# 136khz_RX_2025-06-14.net
KiCad netlist of a schematic drawn in EasyEDA Pro
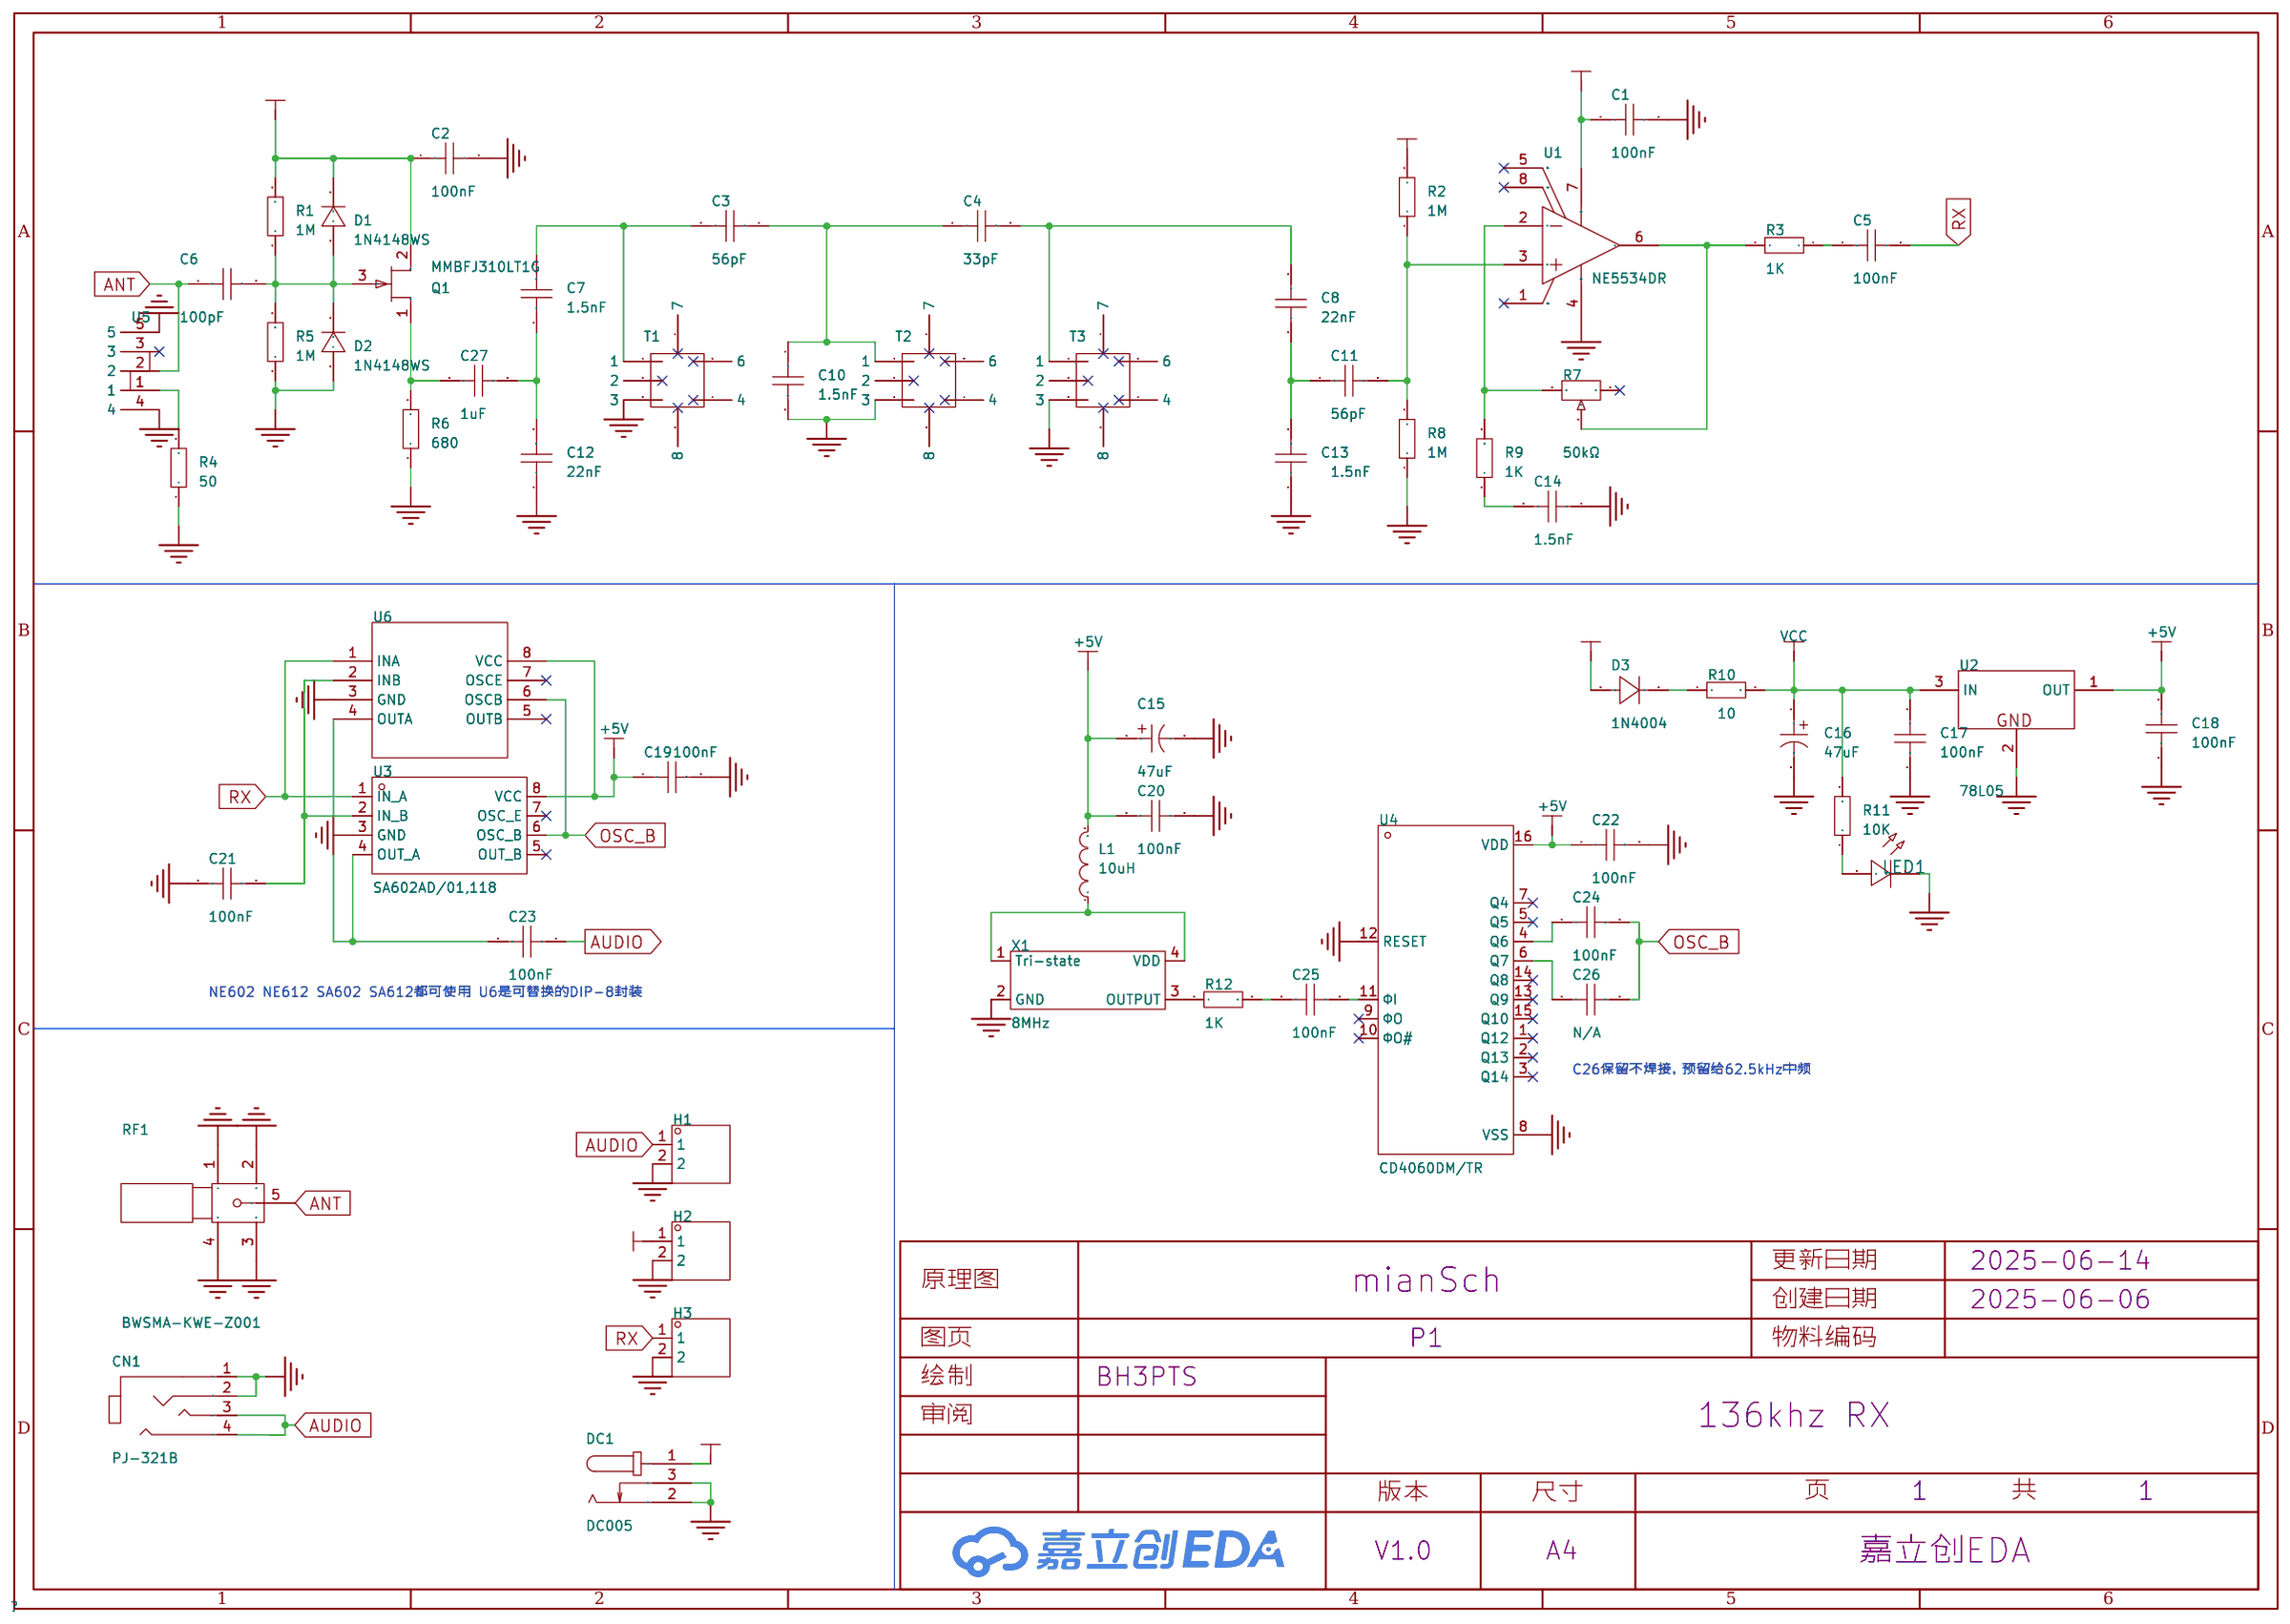
[diagram p0: schematic sheet]

(export (version "E")
  (design (tool "Eeschema 10.0.6"))
  (components
    (comp (ref "C1")
      (value "100nF")
      (footprint "easyedapro:C0805")
      (libsource (lib "easyedapro") (part "CapAcitance"))
    )
    (comp (ref "C2")
      (value "100nF")
      (footprint "easyedapro:C0805")
      (libsource (lib "easyedapro") (part "CapAcitance"))
    )
    (comp (ref "C3")
      (value "56pF")
      (footprint "easyedapro:C0805")
      (libsource (lib "easyedapro") (part "CapAcitance"))
    )
    (comp (ref "C4")
      (value "33pF")
      (footprint "easyedapro:C0805")
      (libsource (lib "easyedapro") (part "CapAcitance"))
    )
    (comp (ref "C5")
      (value "100nF")
      (footprint "easyedapro:C0805")
      (libsource (lib "easyedapro") (part "CapAcitance"))
    )
    (comp (ref "C6")
      (value "100pF")
      (footprint "easyedapro:C0805")
      (libsource (lib "easyedapro") (part "CapAcitance"))
    )
    (comp (ref "C7")
      (value "1.5nF")
      (footprint "easyedapro:C0805")
      (libsource (lib "easyedapro") (part "CapAcitance"))
    )
    (comp (ref "C8")
      (value "22nF")
      (footprint "easyedapro:C0805")
      (libsource (lib "easyedapro") (part "CapAcitance"))
    )
    (comp (ref "C10")
      (value "1.5nF")
      (footprint "easyedapro:C0805")
      (libsource (lib "easyedapro") (part "CapAcitance"))
    )
    (comp (ref "C11")
      (value "56pF")
      (footprint "easyedapro:C0805")
      (libsource (lib "easyedapro") (part "CapAcitance"))
    )
    (comp (ref "C12")
      (value "22nF")
      (footprint "easyedapro:C0805")
      (libsource (lib "easyedapro") (part "CapAcitance"))
    )
    (comp (ref "C13")
      (value "1.5nF")
      (footprint "easyedapro:C0805")
      (libsource (lib "easyedapro") (part "CapAcitance"))
    )
    (comp (ref "C14")
      (value "1.5nF")
      (footprint "easyedapro:C0805")
      (libsource (lib "easyedapro") (part "CapAcitance"))
    )
    (comp (ref "C15")
      (value "47uF")
      (footprint "easyedapro:CAP-SMD_BD6.3-L6.6-W6.6-LS7.2-FD")
      (description "容值:47uF;精度:±20%;额定电压:35V;纹波电流:16.4mA@120Hz;等效串联电阻(ESR):-;")
      (fields
        (field (name "Manufacturer Part") "RVT47UF35V67RV0039")
        (field (name "Manufacturer") "KNSCHA(科尼盛)")
      )
      (libsource (lib "easyedapro") (part "RVT47UF35V67RV0039"))
    )
    (comp (ref "C16")
      (value "47uF")
      (footprint "easyedapro:CAP-SMD_BD6.3-L6.6-W6.6-LS7.2-FD")
      (description "容值:47uF;精度:±20%;额定电压:35V;纹波电流:16.4mA@120Hz;等效串联电阻(ESR):-;")
      (fields
        (field (name "Manufacturer Part") "RVT47UF35V67RV0039")
        (field (name "Manufacturer") "KNSCHA(科尼盛)")
      )
      (libsource (lib "easyedapro") (part "RVT47UF35V67RV0039"))
    )
    (comp (ref "C17")
      (value "100nF")
      (footprint "easyedapro:C0805")
      (libsource (lib "easyedapro") (part "CapAcitance"))
    )
    (comp (ref "C18")
      (value "100nF")
      (footprint "easyedapro:C0805")
      (libsource (lib "easyedapro") (part "CapAcitance"))
    )
    (comp (ref "C19")
      (value "100nF")
      (footprint "easyedapro:C0805")
      (libsource (lib "easyedapro") (part "CapAcitance"))
    )
    (comp (ref "C20")
      (value "100nF")
      (footprint "easyedapro:C0805")
      (libsource (lib "easyedapro") (part "CapAcitance"))
    )
    (comp (ref "C21")
      (value "100nF")
      (footprint "easyedapro:C0805")
      (libsource (lib "easyedapro") (part "CapAcitance"))
    )
    (comp (ref "C22")
      (value "100nF")
      (footprint "easyedapro:C0805")
      (libsource (lib "easyedapro") (part "CapAcitance"))
    )
    (comp (ref "C23")
      (value "100nF")
      (footprint "easyedapro:C0805")
      (libsource (lib "easyedapro") (part "CapAcitance"))
    )
    (comp (ref "C24")
      (value "100nF")
      (footprint "easyedapro:C0805")
      (libsource (lib "easyedapro") (part "CapAcitance"))
    )
    (comp (ref "C25")
      (value "100nF")
      (footprint "easyedapro:C0805")
      (libsource (lib "easyedapro") (part "CapAcitance"))
    )
    (comp (ref "C26")
      (value "N/A")
      (footprint "easyedapro:C0805")
      (libsource (lib "easyedapro") (part "CapAcitance"))
    )
    (comp (ref "C27")
      (value "1uF")
      (footprint "easyedapro:C0805")
      (libsource (lib "easyedapro") (part "CapAcitance"))
    )
    (comp (ref "CN1")
      (value "PJ-321B")
      (footprint "easyedapro:AUDIO-TH_PJ-321B")
      (description "连接器类型:3.5mm耳机座;额定电流:500mA;额定电压:30V;工作温度范围:-20°C~+70°C;焊接温度(最大值):235°C;")
      (fields (field (name "Manufacturer") "XKB Connection(中国星坤)"))
      (libsource (lib "easyedapro") (part "PJ-321B"))
    )
    (comp (ref "D1")
      (value "1N4148WS")
      (footprint "easyedapro:SOD-323_L1.8-W1.3-LS2.5-RD")
      (description "二极管配置:独立式;正向压降(Vf):1.25V@150mA;直流反向耐压(Vr):100V;整流电流:150mA;反向恢复时间(trr):4ns;")
      (fields (field (name "Manufacturer") "CJ(江苏长电/长晶)"))
      (libsource (lib "easyedapro") (part "1N4148WS T4"))
    )
    (comp (ref "D2")
      (value "1N4148WS")
      (footprint "easyedapro:SOD-323_L1.8-W1.3-LS2.5-RD")
      (description "二极管配置:独立式;正向压降(Vf):1.25V@150mA;直流反向耐压(Vr):100V;整流电流:150mA;反向恢复时间(trr):4ns;")
      (fields (field (name "Manufacturer") "CJ(江苏长电/长晶)"))
      (libsource (lib "easyedapro") (part "1N4148WS T4"))
    )
    (comp (ref "D3")
      (value "1N4004")
      (footprint "easyedapro:SMA_L4.4-W2.8-LS5.4-RD")
      (description "二极管配置:独立式;正向压降(Vf):1.1V@1A;直流反向耐压(Vr):400V;整流电流:1A;")
      (fields (field (name "Manufacturer") "TWGMC(台湾迪嘉)"))
      (libsource (lib "easyedapro") (part "1N4004_C727080"))
    )
    (comp (ref "DC1")
      (value "DC005")
      (footprint "easyedapro:DC-IN-TH_DC005")
      (description "连接器类型:DC电源插座;安装方式:弯插;触点内径:2mm;触点外径:6.3mm;额定电流:500mA;额定电压:30V;工作温度范围:-25°C~+70°C;")
      (fields (field (name "Manufacturer") "SHOU HAN(首韩)"))
      (libsource (lib "easyedapro") (part "DC005_C431533"))
    )
    (comp (ref "H1")
      (value "~")
      (footprint "easyedapro:HDR-TH_2P-P2.54-V-M-1")
      (libsource (lib "easyedapro") (part "210S-1*2P L=11.6MMGold-plated black"))
    )
    (comp (ref "H2")
      (value "~")
      (footprint "easyedapro:HDR-TH_2P-P2.54-V-M-1")
      (libsource (lib "easyedapro") (part "210S-1*2P L=11.6MMGold-plated black"))
    )
    (comp (ref "H3")
      (value "~")
      (footprint "easyedapro:HDR-TH_2P-P2.54-V-M-1")
      (libsource (lib "easyedapro") (part "210S-1*2P L=11.6MMGold-plated black"))
    )
    (comp (ref "L1")
      (value "10uH")
      (footprint "easyedapro:L0603")
      (description "电感值:10uH;精度:±10%;额定电流:3mA;饱和电流(Isat):-;直流电阻(DCR):1.85Ω;")
      (fields
        (field (name "Manufacturer Part") "SDFL1608S100KTF")
        (field (name "Manufacturer") "Sunlord(顺络)")
      )
      (libsource (lib "easyedapro") (part "SDFL1608S100KTF"))
    )
    (comp (ref "LED1")
      (value "~")
      (footprint "easyedapro:LED_0603")
      (libsource (lib "easyedapro") (part "LED_R"))
    )
    (comp (ref "Q1")
      (value "MMBFJ310LT1G")
      (footprint "easyedapro:SOT-23-3_L2.9-W1.6-P1.90-LS2.8-BR")
      (description "FET类型:N沟道;栅源击穿电压(V(BR)GSS):-;功率(Pd):-;漏源导通电阻(RDS(on)):-;饱和漏源电流(Idss@Vds,Vgs=0):-;")
      (fields (field (name "Manufacturer") "onsemi(安森美)"))
      (libsource (lib "easyedapro") (part "MMBFJ310LT1G"))
    )
    (comp (ref "R1") (value "1M") (footprint "easyedapro:R0805") (libsource (lib "easyedapro") (part "电阻")))
    (comp (ref "R2") (value "1M") (footprint "easyedapro:R0805") (libsource (lib "easyedapro") (part "电阻")))
    (comp (ref "R3") (value "1K") (footprint "easyedapro:R0805") (libsource (lib "easyedapro") (part "电阻")))
    (comp (ref "R4") (value "50") (footprint "easyedapro:R0805") (libsource (lib "easyedapro") (part "电阻")))
    (comp (ref "R5") (value "1M") (footprint "easyedapro:R0805") (libsource (lib "easyedapro") (part "电阻")))
    (comp (ref "R6") (value "680") (footprint "easyedapro:R0805") (libsource (lib "easyedapro") (part "电阻")))
    (comp (ref "R7")
      (value "50kΩ")
      (footprint "easyedapro:RES-ADJ-TH_3P-L7.1-W6.9-P2.50-L_3362P")
      (description "阻值:50kΩ;精度:±10%;")
      (fields (field (name "Manufacturer Part") "3362P-1-503") (field (name "Manufacturer") "BOCHEN(博晨)"))
      (libsource (lib "easyedapro") (part "3362P-1-503"))
    )
    (comp (ref "R8") (value "1M") (footprint "easyedapro:R0805") (libsource (lib "easyedapro") (part "电阻")))
    (comp (ref "R9") (value "1K") (footprint "easyedapro:R0805") (libsource (lib "easyedapro") (part "电阻")))
    (comp (ref "R10") (value "10") (footprint "easyedapro:R1206") (libsource (lib "easyedapro") (part "电阻")))
    (comp (ref "R11") (value "10K") (footprint "easyedapro:R0805") (libsource (lib "easyedapro") (part "电阻")))
    (comp (ref "R12") (value "1K") (footprint "easyedapro:R0805") (libsource (lib "easyedapro") (part "电阻")))
    (comp (ref "RF1")
      (value "BWSMA-KWE-Z001")
      (footprint "easyedapro:SMA-TH_BWSMA-KWE-Z001")
      (fields (field (name "Manufacturer") "BAT WIRELESS(蝙蝠无线)"))
      (libsource (lib "easyedapro") (part "BWSMA-KWE-Z001"))
    )
    (comp (ref "T1") (value "~") (footprint "easyedapro:TP702") (libsource (lib "easyedapro") (part "TP702")))
    (comp (ref "T2") (value "~") (footprint "easyedapro:TP702") (libsource (lib "easyedapro") (part "TP702")))
    (comp (ref "T3") (value "~") (footprint "easyedapro:TP702") (libsource (lib "easyedapro") (part "TP702")))
    (comp (ref "U1")
      (value "NE5534DR")
      (footprint "easyedapro:SOIC-8_L5.0-W4.0-P1.27-LS6.0-BL")
      (description "放大器数:单路;轨到轨:-;增益带宽积(GBP):-;输入失调电压(Vos):4mV;压摆率(SR):13V/us;输入偏置电流(Ib):1.5uA;")
      (fields (field (name "Manufacturer") "TI(德州仪器)"))
      (libsource (lib "easyedapro") (part "NE5534DR"))
    )
    (comp (ref "U2")
      (value "78L05")
      (footprint "easyedapro:SOT-89-3_L4.5-W2.5-P1.50-LS4.2-BR")
      (description "输出类型:固定;最大输入电压:30V;输出电压:5V;输出电流:100mA;电源纹波抑制比(PSRR):49dB@(120Hz);输出极性:正极;")
      (fields (field (name "Manufacturer") "UMW(友台半导体)"))
      (libsource (lib "easyedapro") (part "UMW78L05"))
    )
    (comp (ref "U3")
      (value "SA602AD/01,118")
      (footprint "easyedapro:SOP-8_L4.9-W3.9-P1.27-LS6.0-BL")
      (description "应用领域:手机；VHF；UHF；HF;频率范围:-;增益:17dB;噪声系数:5dB;")
      (fields (field (name "Manufacturer") "NXP(恩智浦)"))
      (libsource (lib "easyedapro") (part "SA602AD/01,118"))
    )
    (comp (ref "U4")
      (value "CD4060DM/TR")
      (footprint "easyedapro:SOP-16_L9.9-W3.9-P1.27-LS6.0-BL")
      (description "CD4000系列  CMOS 14 级纹波进位二进制计数器/除法器和振荡器")
      (fields (field (name "Manufacturer") "HGSEMI(华冠)"))
      (libsource (lib "easyedapro") (part "CD4060DM/TR"))
    )
    (comp (ref "U5")
      (value "~")
      (footprint "easyedapro:SS-12D07G3")
      (description "3脚2档 柄高3MM")
      (libsource (lib "easyedapro") (part "SS-12D07G3"))
    )
    (comp (ref "U6")
      (value "~")
      (footprint "easyedapro:DIP-8_L9.2-W6.4-P2.54-LS7.6-BL")
      (fields (field (name "Manufacturer") "ddsddp-"))
      (libsource (lib "easyedapro") (part "ne602"))
    )
    (comp (ref "X1")
      (value "8MHz")
      (footprint "easyedapro:OSC-SMD_4P-L3.2-W2.5-BL")
      (description "频率:8MHz;常温频差:±10ppm;输出模式:CMOS;工作电压:5V;频率稳定度:±20ppm;")
      (fields
        (field (name "Manufacturer Part") "OH2EL89CFI-111YLC-8M")
        (field (name "Manufacturer") "YXC(扬兴晶振)")
      )
      (libsource (lib "easyedapro") (part "OH2EL89CFI-111YLC-8M"))
    )
  )
  (nets
    (net (code "1") (name "+5V") (class "Default")
      (node (ref "C15") (pin "1") (pinfunction "1_1") (pintype "input"))
      (node (ref "C18") (pin "2") (pinfunction "2_2") (pintype "input"))
      (node (ref "C19") (pin "1") (pinfunction "1_1") (pintype "input"))
      (node (ref "C20") (pin "2") (pinfunction "2_2") (pintype "input"))
      (node (ref "C22") (pin "1") (pinfunction "1_1") (pintype "input"))
      (node (ref "L1") (pin "2") (pinfunction "2_2") (pintype "unspecified"))
      (node (ref "U2") (pin "1") (pinfunction "OUT_1") (pintype "unspecified"))
      (node (ref "U3") (pin "8") (pinfunction "VCC_8") (pintype "unspecified"))
      (node (ref "U4") (pin "16") (pinfunction "VDD_16") (pintype "unspecified"))
      (node (ref "U6") (pin "8") (pinfunction "VCC_8") (pintype "input"))
    )
    (net (code "2") (name "ANT") (class "Default")
      (node (ref "C6") (pin "1") (pinfunction "1_1") (pintype "input"))
      (node (ref "RF1") (pin "5") (pinfunction "5_5") (pintype "unspecified"))
      (node (ref "U5") (pin "2") (pinfunction "2_2") (pintype "input"))
    )
    (net (code "3") (name "AUDIO") (class "Default")
      (node (ref "C23") (pin "1") (pinfunction "1_1") (pintype "input"))
      (node (ref "CN1") (pin "3") (pinfunction "3_3") (pintype "unspecified"))
      (node (ref "CN1") (pin "4") (pinfunction "4_4") (pintype "unspecified"))
      (node (ref "H1") (pin "1") (pinfunction "1_1") (pintype "unspecified"))
    )
    (net (code "4") (name "GND") (class "Default")
      (node (ref "C1") (pin "2") (pinfunction "2_2") (pintype "input"))
      (node (ref "C10") (pin "2") (pinfunction "2_2") (pintype "input"))
      (node (ref "C12") (pin "1") (pinfunction "1_1") (pintype "input"))
      (node (ref "C13") (pin "1") (pinfunction "1_1") (pintype "input"))
      (node (ref "C14") (pin "1") (pinfunction "1_1") (pintype "input"))
      (node (ref "C15") (pin "2") (pinfunction "2_2") (pintype "input"))
      (node (ref "C16") (pin "2") (pinfunction "2_2") (pintype "input"))
      (node (ref "C17") (pin "1") (pinfunction "1_1") (pintype "input"))
      (node (ref "C18") (pin "1") (pinfunction "1_1") (pintype "input"))
      (node (ref "C19") (pin "2") (pinfunction "2_2") (pintype "input"))
      (node (ref "C2") (pin "2") (pinfunction "2_2") (pintype "input"))
      (node (ref "C20") (pin "1") (pinfunction "1_1") (pintype "input"))
      (node (ref "C21") (pin "1") (pinfunction "1_1") (pintype "input"))
      (node (ref "C22") (pin "2") (pinfunction "2_2") (pintype "input"))
      (node (ref "CN1") (pin "1") (pinfunction "1_1") (pintype "unspecified"))
      (node (ref "CN1") (pin "2") (pinfunction "2_2") (pintype "unspecified"))
      (node (ref "D2") (pin "2") (pinfunction "A_2") (pintype "unspecified"))
      (node (ref "DC1") (pin "2") (pinfunction "2_2") (pintype "unspecified"))
      (node (ref "DC1") (pin "3") (pinfunction "3_3") (pintype "unspecified"))
      (node (ref "H1") (pin "2") (pinfunction "2_2") (pintype "unspecified"))
      (node (ref "H2") (pin "2") (pinfunction "2_2") (pintype "unspecified"))
      (node (ref "H3") (pin "2") (pinfunction "2_2") (pintype "unspecified"))
      (node (ref "LED1") (pin "1") (pinfunction "C_1") (pintype "input"))
      (node (ref "R4") (pin "1") (pinfunction "1_1") (pintype "input"))
      (node (ref "R5") (pin "1") (pinfunction "1_1") (pintype "input"))
      (node (ref "R6") (pin "1") (pinfunction "1_1") (pintype "input"))
      (node (ref "R8") (pin "1") (pinfunction "1_1") (pintype "input"))
      (node (ref "RF1") (pin "1") (pinfunction "1_1") (pintype "unspecified"))
      (node (ref "RF1") (pin "2") (pinfunction "2_2") (pintype "unspecified"))
      (node (ref "RF1") (pin "3") (pinfunction "3_3") (pintype "unspecified"))
      (node (ref "RF1") (pin "4") (pinfunction "4_4") (pintype "unspecified"))
      (node (ref "T1") (pin "3") (pinfunction "3_3") (pintype "input"))
      (node (ref "T2") (pin "3") (pinfunction "3_3") (pintype "input"))
      (node (ref "T3") (pin "3") (pinfunction "3_3") (pintype "input"))
      (node (ref "U1") (pin "4") (pinfunction "VCC-_4") (pintype "unspecified"))
      (node (ref "U2") (pin "2") (pinfunction "GND_2") (pintype "unspecified"))
      (node (ref "U3") (pin "3") (pinfunction "GND_3") (pintype "unspecified"))
      (node (ref "U4") (pin "12") (pinfunction "RESET_12") (pintype "unspecified"))
      (node (ref "U4") (pin "8") (pinfunction "VSS_8") (pintype "unspecified"))
      (node (ref "U5") (pin "4") (pinfunction "4_4") (pintype "input"))
      (node (ref "U5") (pin "5") (pinfunction "5_5") (pintype "input"))
      (node (ref "U6") (pin "3") (pinfunction "GND_3") (pintype "input"))
      (node (ref "X1") (pin "2") (pinfunction "GND_2") (pintype "unspecified"))
    )
    (net (code "5") (name "Net-(C3-Pad2)") (class "Default")
      (node (ref "C3") (pin "2") (pinfunction "2_2") (pintype "input"))
      (node (ref "C7") (pin "2") (pinfunction "2_2") (pintype "input"))
      (node (ref "T1") (pin "1") (pinfunction "1_1") (pintype "input"))
    )
    (net (code "6") (name "Net-(C4-Pad2)") (class "Default")
      (node (ref "C4") (pin "2") (pinfunction "2_2") (pintype "input"))
      (node (ref "C8") (pin "2") (pinfunction "2_2") (pintype "input"))
      (node (ref "T3") (pin "1") (pinfunction "1_1") (pintype "input"))
    )
    (net (code "7") (name "Net-(C5-Pad1)") (class "Default")
      (node (ref "C5") (pin "1") (pinfunction "1_1") (pintype "input"))
      (node (ref "R3") (pin "1") (pinfunction "1_1") (pintype "input"))
    )
    (net (code "8") (name "Net-(C10-Pad1)") (class "Default")
      (node (ref "C10") (pin "1") (pinfunction "1_1") (pintype "input"))
      (node (ref "C3") (pin "1") (pinfunction "1_1") (pintype "input"))
      (node (ref "C4") (pin "1") (pinfunction "1_1") (pintype "input"))
      (node (ref "T2") (pin "1") (pinfunction "1_1") (pintype "input"))
    )
    (net (code "9") (name "Net-(C11-Pad1)") (class "Default")
      (node (ref "C11") (pin "1") (pinfunction "1_1") (pintype "input"))
      (node (ref "C13") (pin "2") (pinfunction "2_2") (pintype "input"))
      (node (ref "C8") (pin "1") (pinfunction "1_1") (pintype "input"))
    )
    (net (code "10") (name "Net-(C12-Pad2)") (class "Default")
      (node (ref "C12") (pin "2") (pinfunction "2_2") (pintype "input"))
      (node (ref "C27") (pin "2") (pinfunction "2_2") (pintype "input"))
      (node (ref "C7") (pin "1") (pinfunction "1_1") (pintype "input"))
    )
    (net (code "11") (name "Net-(C14-Pad2)") (class "Default")
      (node (ref "C14") (pin "2") (pinfunction "2_2") (pintype "input"))
      (node (ref "R9") (pin "1") (pinfunction "1_1") (pintype "input"))
    )
    (net (code "12") (name "Net-(C25-Pad1)") (class "Default")
      (node (ref "C25") (pin "1") (pinfunction "1_1") (pintype "input"))
      (node (ref "R12") (pin "2") (pinfunction "2_2") (pintype "input"))
    )
    (net (code "13") (name "Net-(D1-A)") (class "Default")
      (node (ref "C6") (pin "2") (pinfunction "2_2") (pintype "input"))
      (node (ref "D1") (pin "2") (pinfunction "A_2") (pintype "unspecified"))
      (node (ref "D2") (pin "1") (pinfunction "K_1") (pintype "unspecified"))
      (node (ref "Q1") (pin "3") (pinfunction "G_3") (pintype "unspecified"))
      (node (ref "R1") (pin "1") (pinfunction "1_1") (pintype "input"))
      (node (ref "R5") (pin "2") (pinfunction "2_2") (pintype "input"))
    )
    (net (code "14") (name "Net-(D3-K)") (class "Default")
      (node (ref "D3") (pin "1") (pinfunction "K_1") (pintype "unspecified"))
      (node (ref "R10") (pin "1") (pinfunction "1_1") (pintype "input"))
    )
    (net (code "15") (name "Net-(LED1-A)") (class "Default")
      (node (ref "LED1") (pin "2") (pinfunction "A_2") (pintype "input"))
      (node (ref "R11") (pin "1") (pinfunction "1_1") (pintype "input"))
    )
    (net (code "16") (name "Net-(Q1-D)") (class "Default")
      (node (ref "C27") (pin "1") (pinfunction "1_1") (pintype "input"))
      (node (ref "Q1") (pin "1") (pinfunction "D_1") (pintype "unspecified"))
      (node (ref "R6") (pin "2") (pinfunction "2_2") (pintype "input"))
    )
    (net (code "17") (name "Net-(R4-Pad2)") (class "Default")
      (node (ref "R4") (pin "2") (pinfunction "2_2") (pintype "input"))
      (node (ref "U5") (pin "1") (pinfunction "1_1") (pintype "input"))
    )
    (net (code "18") (name "Net-(U1-IN+)") (class "Default")
      (node (ref "C11") (pin "2") (pinfunction "2_2") (pintype "input"))
      (node (ref "R2") (pin "1") (pinfunction "1_1") (pintype "input"))
      (node (ref "R8") (pin "2") (pinfunction "2_2") (pintype "input"))
      (node (ref "U1") (pin "3") (pinfunction "IN+_3") (pintype "unspecified"))
    )
    (net (code "19") (name "Net-(U1-IN-)") (class "Default")
      (node (ref "R7") (pin "3") (pinfunction "3_3") (pintype "input"))
      (node (ref "R9") (pin "2") (pinfunction "2_2") (pintype "input"))
      (node (ref "U1") (pin "2") (pinfunction "IN-_2") (pintype "unspecified"))
    )
    (net (code "20") (name "Net-(U1-OUT)") (class "Default")
      (node (ref "R3") (pin "2") (pinfunction "2_2") (pintype "input"))
      (node (ref "R7") (pin "2") (pinfunction "2_2") (pintype "input"))
      (node (ref "U1") (pin "6") (pinfunction "OUT_6") (pintype "output"))
    )
    (net (code "21") (name "Net-(U3-IN_B)") (class "Default")
      (node (ref "C21") (pin "2") (pinfunction "2_2") (pintype "input"))
      (node (ref "U3") (pin "2") (pinfunction "IN_B_2") (pintype "unspecified"))
      (node (ref "U6") (pin "2") (pinfunction "INB_2") (pintype "input"))
    )
    (net (code "22") (name "Net-(U3-OUT_A)") (class "Default")
      (node (ref "C23") (pin "2") (pinfunction "2_2") (pintype "input"))
      (node (ref "U3") (pin "4") (pinfunction "OUT_A_4") (pintype "unspecified"))
      (node (ref "U6") (pin "4") (pinfunction "OUTA_4") (pintype "input"))
    )
    (net (code "23") (name "Net-(U4-Q6)") (class "Default")
      (node (ref "C24") (pin "1") (pinfunction "1_1") (pintype "input"))
      (node (ref "U4") (pin "4") (pinfunction "Q6_4") (pintype "unspecified"))
    )
    (net (code "24") (name "Net-(U4-Q7)") (class "Default")
      (node (ref "C26") (pin "1") (pinfunction "1_1") (pintype "input"))
      (node (ref "U4") (pin "6") (pinfunction "Q7_6") (pintype "unspecified"))
    )
    (net (code "25") (name "Net-(U4-ФI)") (class "Default")
      (node (ref "C25") (pin "2") (pinfunction "2_2") (pintype "input"))
      (node (ref "U4") (pin "11") (pinfunction "ФI_11") (pintype "unspecified"))
    )
    (net (code "26") (name "Net-(X1-OUTPUT)") (class "Default")
      (node (ref "R12") (pin "1") (pinfunction "1_1") (pintype "input"))
      (node (ref "X1") (pin "3") (pinfunction "OUTPUT_3") (pintype "unspecified"))
    )
    (net (code "27") (name "Net-(X1-Tri-state)") (class "Default")
      (node (ref "L1") (pin "1") (pinfunction "1_1") (pintype "unspecified"))
      (node (ref "X1") (pin "1") (pinfunction "Tri-state_1") (pintype "unspecified"))
      (node (ref "X1") (pin "4") (pinfunction "VDD_4") (pintype "unspecified"))
    )
    (net (code "28") (name "OSC_B") (class "Default")
      (node (ref "C24") (pin "2") (pinfunction "2_2") (pintype "input"))
      (node (ref "C26") (pin "2") (pinfunction "2_2") (pintype "input"))
      (node (ref "U3") (pin "6") (pinfunction "OSC_B_6") (pintype "unspecified"))
      (node (ref "U6") (pin "6") (pinfunction "OSCB_6") (pintype "input"))
    )
    (net (code "29") (name "RX") (class "Default")
      (node (ref "C5") (pin "2") (pinfunction "2_2") (pintype "input"))
      (node (ref "H3") (pin "1") (pinfunction "1_1") (pintype "unspecified"))
      (node (ref "U3") (pin "1") (pinfunction "IN_A_1") (pintype "unspecified"))
      (node (ref "U6") (pin "1") (pinfunction "INA_1") (pintype "input"))
    )
    (net (code "30") (name "VCC") (class "Default")
      (node (ref "C1") (pin "1") (pinfunction "1_1") (pintype "input"))
      (node (ref "C16") (pin "1") (pinfunction "1_1") (pintype "input"))
      (node (ref "C17") (pin "2") (pinfunction "2_2") (pintype "input"))
      (node (ref "C2") (pin "1") (pinfunction "1_1") (pintype "input"))
      (node (ref "D1") (pin "1") (pinfunction "K_1") (pintype "unspecified"))
      (node (ref "Q1") (pin "2") (pinfunction "S_2") (pintype "unspecified"))
      (node (ref "R1") (pin "2") (pinfunction "2_2") (pintype "input"))
      (node (ref "R10") (pin "2") (pinfunction "2_2") (pintype "input"))
      (node (ref "R11") (pin "2") (pinfunction "2_2") (pintype "input"))
      (node (ref "R2") (pin "2") (pinfunction "2_2") (pintype "input"))
      (node (ref "U1") (pin "7") (pinfunction "VCC+_7") (pintype "unspecified"))
      (node (ref "U2") (pin "3") (pinfunction "IN_3") (pintype "unspecified"))
    )
    (net (code "31") (name "VIN") (class "Default")
      (node (ref "D3") (pin "2") (pinfunction "A_2") (pintype "unspecified"))
      (node (ref "DC1") (pin "1") (pinfunction "1_1") (pintype "unspecified"))
      (node (ref "H2") (pin "1") (pinfunction "1_1") (pintype "unspecified"))
    )
    (net (code "32") (name "unconnected-(R7-Pad1)") (class "Default")
      (node (ref "R7") (pin "1") (pinfunction "1_1") (pintype "input+no_connect"))
    )
    (net (code "33") (name "unconnected-(T1-Pad2)") (class "Default")
      (node (ref "T1") (pin "2") (pinfunction "2_2") (pintype "input+no_connect"))
    )
    (net (code "34") (name "unconnected-(T1-Pad4)") (class "Default")
      (node (ref "T1") (pin "4") (pinfunction "4_4") (pintype "input+no_connect"))
    )
    (net (code "35") (name "unconnected-(T1-Pad6)") (class "Default")
      (node (ref "T1") (pin "6") (pinfunction "6_6") (pintype "input+no_connect"))
    )
    (net (code "36") (name "unconnected-(T1-Pad7)") (class "Default")
      (node (ref "T1") (pin "7") (pinfunction "7_7") (pintype "input+no_connect"))
    )
    (net (code "37") (name "unconnected-(T1-Pad8)") (class "Default")
      (node (ref "T1") (pin "8") (pinfunction "8_8") (pintype "input+no_connect"))
    )
    (net (code "38") (name "unconnected-(T2-Pad2)") (class "Default")
      (node (ref "T2") (pin "2") (pinfunction "2_2") (pintype "input+no_connect"))
    )
    (net (code "39") (name "unconnected-(T2-Pad4)") (class "Default")
      (node (ref "T2") (pin "4") (pinfunction "4_4") (pintype "input+no_connect"))
    )
    (net (code "40") (name "unconnected-(T2-Pad6)") (class "Default")
      (node (ref "T2") (pin "6") (pinfunction "6_6") (pintype "input+no_connect"))
    )
    (net (code "41") (name "unconnected-(T2-Pad7)") (class "Default")
      (node (ref "T2") (pin "7") (pinfunction "7_7") (pintype "input+no_connect"))
    )
    (net (code "42") (name "unconnected-(T2-Pad8)") (class "Default")
      (node (ref "T2") (pin "8") (pinfunction "8_8") (pintype "input+no_connect"))
    )
    (net (code "43") (name "unconnected-(T3-Pad2)") (class "Default")
      (node (ref "T3") (pin "2") (pinfunction "2_2") (pintype "input+no_connect"))
    )
    (net (code "44") (name "unconnected-(T3-Pad4)") (class "Default")
      (node (ref "T3") (pin "4") (pinfunction "4_4") (pintype "input+no_connect"))
    )
    (net (code "45") (name "unconnected-(T3-Pad6)") (class "Default")
      (node (ref "T3") (pin "6") (pinfunction "6_6") (pintype "input+no_connect"))
    )
    (net (code "46") (name "unconnected-(T3-Pad7)") (class "Default")
      (node (ref "T3") (pin "7") (pinfunction "7_7") (pintype "input+no_connect"))
    )
    (net (code "47") (name "unconnected-(T3-Pad8)") (class "Default")
      (node (ref "T3") (pin "8") (pinfunction "8_8") (pintype "input+no_connect"))
    )
    (net (code "48") (name "unconnected-(U1-BALANCE-Pad1)") (class "Default")
      (node (ref "U1") (pin "1") (pinfunction "BALANCE_1") (pintype "unspecified+no_connect"))
    )
    (net (code "49") (name "unconnected-(U1-COMP-Pad5)") (class "Default")
      (node (ref "U1") (pin "5") (pinfunction "COMP_5") (pintype "unspecified+no_connect"))
    )
    (net (code "50") (name "unconnected-(U1-COMPBAL-Pad8)") (class "Default")
      (node (ref "U1") (pin "8") (pinfunction "COMPBAL_8") (pintype "unspecified+no_connect"))
    )
    (net (code "51") (name "unconnected-(U3-OSC_E-Pad7)") (class "Default")
      (node (ref "U3") (pin "7") (pinfunction "OSC_E_7") (pintype "unspecified+no_connect"))
    )
    (net (code "52") (name "unconnected-(U3-OUT_B-Pad5)") (class "Default")
      (node (ref "U3") (pin "5") (pinfunction "OUT_B_5") (pintype "unspecified+no_connect"))
    )
    (net (code "53") (name "unconnected-(U4-Q4-Pad7)") (class "Default")
      (node (ref "U4") (pin "7") (pinfunction "Q4_7") (pintype "unspecified+no_connect"))
    )
    (net (code "54") (name "unconnected-(U4-Q5-Pad5)") (class "Default")
      (node (ref "U4") (pin "5") (pinfunction "Q5_5") (pintype "unspecified+no_connect"))
    )
    (net (code "55") (name "unconnected-(U4-Q8-Pad14)") (class "Default")
      (node (ref "U4") (pin "14") (pinfunction "Q8_14") (pintype "unspecified+no_connect"))
    )
    (net (code "56") (name "unconnected-(U4-Q9-Pad13)") (class "Default")
      (node (ref "U4") (pin "13") (pinfunction "Q9_13") (pintype "unspecified+no_connect"))
    )
    (net (code "57") (name "unconnected-(U4-Q10-Pad15)") (class "Default")
      (node (ref "U4") (pin "15") (pinfunction "Q10_15") (pintype "unspecified+no_connect"))
    )
    (net (code "58") (name "unconnected-(U4-Q12-Pad1)") (class "Default")
      (node (ref "U4") (pin "1") (pinfunction "Q12_1") (pintype "unspecified+no_connect"))
    )
    (net (code "59") (name "unconnected-(U4-Q13-Pad2)") (class "Default")
      (node (ref "U4") (pin "2") (pinfunction "Q13_2") (pintype "unspecified+no_connect"))
    )
    (net (code "60") (name "unconnected-(U4-Q14-Pad3)") (class "Default")
      (node (ref "U4") (pin "3") (pinfunction "Q14_3") (pintype "unspecified+no_connect"))
    )
    (net (code "61") (name "unconnected-(U4-ФO#-Pad10)") (class "Default")
      (node (ref "U4") (pin "10") (pinfunction "ФO#_10") (pintype "unspecified+no_connect"))
    )
    (net (code "62") (name "unconnected-(U4-ФO-Pad9)") (class "Default")
      (node (ref "U4") (pin "9") (pinfunction "ФO_9") (pintype "unspecified+no_connect"))
    )
    (net (code "63") (name "unconnected-(U5-Pad3)") (class "Default")
      (node (ref "U5") (pin "3") (pinfunction "3_3") (pintype "input+no_connect"))
    )
    (net (code "64") (name "unconnected-(U6-OSCE-Pad7)") (class "Default")
      (node (ref "U6") (pin "7") (pinfunction "OSCE_7") (pintype "input+no_connect"))
    )
    (net (code "65") (name "unconnected-(U6-OUTB-Pad5)") (class "Default")
      (node (ref "U6") (pin "5") (pinfunction "OUTB_5") (pintype "input+no_connect"))
    )
  )
)
